# Switches.net
KiCad netlist of a schematic drawn in Altium Designer
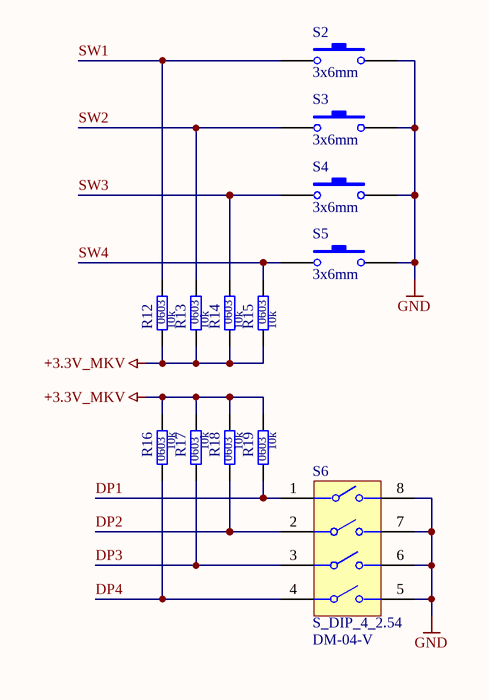
[diagram p0: Switches.SchDoc]

(export (version "E")
  (design (tool "Eeschema 10.0.6"))
  (components
    (comp (ref "R12")
      (value "10k")
      (footprint "R_0603_1608")
      (fields
        (field (name "SCH_FOOTPRINT") "0603")
        (field (name "PART NUMBER") "R_10k_0603_1")
        (field (name "VOLTAGE") "75V")
        (field (name "POWER") "100mW")
      )
      (libsource (lib "Library") (part "R"))
    )
    (comp (ref "R13")
      (value "10k")
      (footprint "R_0603_1608")
      (fields
        (field (name "SCH_FOOTPRINT") "0603")
        (field (name "PART NUMBER") "R_10k_0603_1")
        (field (name "VOLTAGE") "75V")
        (field (name "POWER") "100mW")
      )
      (libsource (lib "Library") (part "R"))
    )
    (comp (ref "R14")
      (value "10k")
      (footprint "R_0603_1608")
      (fields
        (field (name "SCH_FOOTPRINT") "0603")
        (field (name "PART NUMBER") "R_10k_0603_1")
        (field (name "VOLTAGE") "75V")
        (field (name "POWER") "100mW")
      )
      (libsource (lib "Library") (part "R"))
    )
    (comp (ref "R15")
      (value "10k")
      (footprint "R_0603_1608")
      (fields
        (field (name "SCH_FOOTPRINT") "0603")
        (field (name "PART NUMBER") "R_10k_0603_1")
        (field (name "VOLTAGE") "75V")
        (field (name "POWER") "100mW")
      )
      (libsource (lib "Library") (part "R"))
    )
    (comp (ref "R16")
      (value "10k")
      (footprint "R_0603_1608")
      (fields
        (field (name "SCH_FOOTPRINT") "0603")
        (field (name "PART NUMBER") "R_10k_0603_1")
        (field (name "VOLTAGE") "75V")
        (field (name "POWER") "100mW")
      )
      (libsource (lib "Library") (part "R"))
    )
    (comp (ref "R17")
      (value "10k")
      (footprint "R_0603_1608")
      (fields
        (field (name "SCH_FOOTPRINT") "0603")
        (field (name "PART NUMBER") "R_10k_0603_1")
        (field (name "VOLTAGE") "75V")
        (field (name "POWER") "100mW")
      )
      (libsource (lib "Library") (part "R"))
    )
    (comp (ref "R18")
      (value "10k")
      (footprint "R_0603_1608")
      (fields
        (field (name "SCH_FOOTPRINT") "0603")
        (field (name "PART NUMBER") "R_10k_0603_1")
        (field (name "VOLTAGE") "75V")
        (field (name "POWER") "100mW")
      )
      (libsource (lib "Library") (part "R"))
    )
    (comp (ref "R19")
      (value "10k")
      (footprint "R_0603_1608")
      (fields
        (field (name "SCH_FOOTPRINT") "0603")
        (field (name "PART NUMBER") "R_10k_0603_1")
        (field (name "VOLTAGE") "75V")
        (field (name "POWER") "100mW")
      )
      (libsource (lib "Library") (part "R"))
    )
    (comp (ref "S2")
      (value "3x6mm")
      (footprint "S_TACTSWITCH3x6")
      (description "Tact Switch")
      (fields
        (field (name "PART NUMBER") "S_TACTSWITCH")
        (field (name "SCH_FOOTPRINT") "3x6mm")
        (field (name "MANUFACTURER") "Ninigi")
      )
      (libsource (lib "Library") (part "S_TACTSWITCH"))
    )
    (comp (ref "S3")
      (value "3x6mm")
      (footprint "S_TACTSWITCH3x6")
      (description "Tact Switch")
      (fields
        (field (name "PART NUMBER") "S_TACTSWITCH")
        (field (name "SCH_FOOTPRINT") "3x6mm")
        (field (name "MANUFACTURER") "Ninigi")
      )
      (libsource (lib "Library") (part "S_TACTSWITCH"))
    )
    (comp (ref "S4")
      (value "3x6mm")
      (footprint "S_TACTSWITCH3x6")
      (description "Tact Switch")
      (fields
        (field (name "PART NUMBER") "S_TACTSWITCH")
        (field (name "SCH_FOOTPRINT") "3x6mm")
        (field (name "MANUFACTURER") "Ninigi")
      )
      (libsource (lib "Library") (part "S_TACTSWITCH"))
    )
    (comp (ref "S5")
      (value "3x6mm")
      (footprint "S_TACTSWITCH3x6")
      (description "Tact Switch")
      (fields
        (field (name "PART NUMBER") "S_TACTSWITCH")
        (field (name "SCH_FOOTPRINT") "3x6mm")
        (field (name "MANUFACTURER") "Ninigi")
      )
      (libsource (lib "Library") (part "S_TACTSWITCH"))
    )
    (comp (ref "S6")
      (value "DM-04-V")
      (footprint "S_DIP_4_2.54")
      (fields
        (field (name "PART NUMBER") "S_DM-04-V")
        (field (name "SCH_FOOTPRINT") "S_DIP_4_2.54")
        (field (name "MANUFACTURER") "DIPTRONICS")
        (field (name "Comment") "DIP SWITCH 4 POS")
      )
      (libsource (lib "Library") (part "S_A6H-4101"))
    )
  )
  (nets
    (net (code "1") (name "+3.3V_MKV") (class "Default")
      (node (ref "R12") (pin "1") (pinfunction "1_1") (pintype "passive"))
      (node (ref "R13") (pin "1") (pinfunction "1_1") (pintype "passive"))
      (node (ref "R14") (pin "1") (pinfunction "1_1") (pintype "passive"))
      (node (ref "R15") (pin "1") (pinfunction "1_1") (pintype "passive"))
      (node (ref "R16") (pin "1") (pinfunction "1_1") (pintype "passive"))
      (node (ref "R17") (pin "1") (pinfunction "1_1") (pintype "passive"))
      (node (ref "R18") (pin "1") (pinfunction "1_1") (pintype "passive"))
      (node (ref "R19") (pin "1") (pinfunction "1_1") (pintype "passive"))
    )
    (net (code "2") (name "/DP1") (class "Default")
      (node (ref "R19") (pin "2") (pinfunction "2_2") (pintype "passive"))
      (node (ref "S6") (pin "1") (pinfunction "1_1") (pintype "passive"))
    )
    (net (code "3") (name "/DP2") (class "Default")
      (node (ref "R18") (pin "2") (pinfunction "2_2") (pintype "passive"))
      (node (ref "S6") (pin "2") (pinfunction "2_2") (pintype "passive"))
    )
    (net (code "4") (name "/DP3") (class "Default")
      (node (ref "R17") (pin "2") (pinfunction "2_2") (pintype "passive"))
      (node (ref "S6") (pin "3") (pinfunction "3_3") (pintype "passive"))
    )
    (net (code "5") (name "/DP4") (class "Default")
      (node (ref "R16") (pin "2") (pinfunction "2_2") (pintype "passive"))
      (node (ref "S6") (pin "4") (pinfunction "4_4") (pintype "passive"))
    )
    (net (code "6") (name "/SW1") (class "Default")
      (node (ref "R12") (pin "2") (pinfunction "2_2") (pintype "passive"))
      (node (ref "S2") (pin "1") (pinfunction "1_1") (pintype "passive"))
    )
    (net (code "7") (name "/SW2") (class "Default")
      (node (ref "R13") (pin "2") (pinfunction "2_2") (pintype "passive"))
      (node (ref "S3") (pin "1") (pinfunction "1_1") (pintype "passive"))
    )
    (net (code "8") (name "/SW3") (class "Default")
      (node (ref "R14") (pin "2") (pinfunction "2_2") (pintype "passive"))
      (node (ref "S4") (pin "1") (pinfunction "1_1") (pintype "passive"))
    )
    (net (code "9") (name "/SW4") (class "Default")
      (node (ref "R15") (pin "2") (pinfunction "2_2") (pintype "passive"))
      (node (ref "S5") (pin "1") (pinfunction "1_1") (pintype "passive"))
    )
    (net (code "10") (name "GND") (class "Default")
      (node (ref "S2") (pin "2") (pinfunction "2_2") (pintype "passive"))
      (node (ref "S3") (pin "2") (pinfunction "2_2") (pintype "passive"))
      (node (ref "S4") (pin "2") (pinfunction "2_2") (pintype "passive"))
      (node (ref "S5") (pin "2") (pinfunction "2_2") (pintype "passive"))
      (node (ref "S6") (pin "5") (pinfunction "5_5") (pintype "passive"))
      (node (ref "S6") (pin "6") (pinfunction "6_6") (pintype "passive"))
      (node (ref "S6") (pin "7") (pinfunction "7_7") (pintype "passive"))
      (node (ref "S6") (pin "8") (pinfunction "8_8") (pintype "passive"))
    )
  )
)
